# Sheet1.net
KiCad netlist of a schematic drawn in Altium Designer
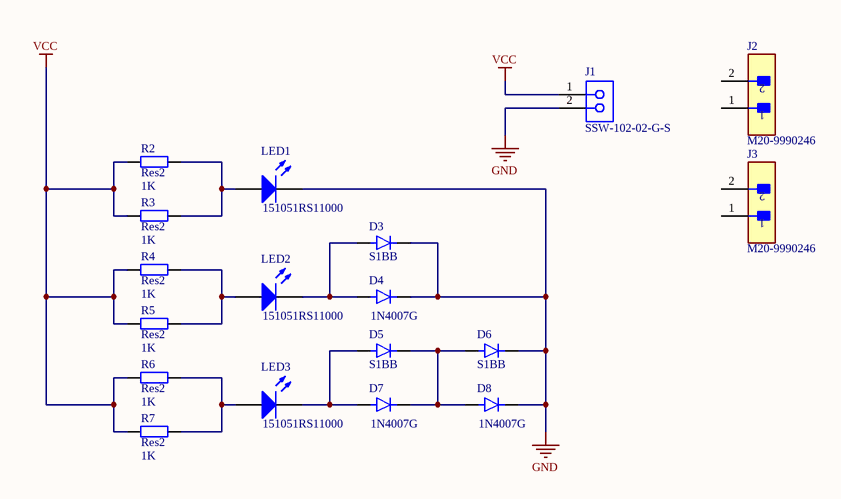
[diagram p0: Sheet1.SchDoc]

(export (version "E")
  (design (tool "Eeschema 10.0.6"))
  (components
    (comp (ref "D3")
      (value "S1BB")
      (footprint "S1BB:DIOM4336X265N")
      (fields (field (name "MF") "{'manufacturer': u'Taiwan Semiconductor'}"))
      (libsource (lib "*") (part "S1BB"))
    )
    (comp (ref "D4")
      (value "1N4007G")
      (footprint "1N4007G:DIOAD1036W78L470D235")
      (fields (field (name "MF") "{'manufacturer': u'ON Semiconductor'}"))
      (libsource (lib "*") (part "1N4007G"))
    )
    (comp (ref "D5")
      (value "S1BB")
      (footprint "S1BB:DIOM4336X265N")
      (fields (field (name "MF") "{'manufacturer': u'Taiwan Semiconductor'}"))
      (libsource (lib "*") (part "S1BB"))
    )
    (comp (ref "D6")
      (value "S1BB")
      (footprint "S1BB:DIOM4336X265N")
      (fields (field (name "MF") "{'manufacturer': u'Taiwan Semiconductor'}"))
      (libsource (lib "*") (part "S1BB"))
    )
    (comp (ref "D7")
      (value "1N4007G")
      (footprint "1N4007G:DIOAD1036W78L470D235")
      (fields (field (name "MF") "{'manufacturer': u'ON Semiconductor'}"))
      (libsource (lib "*") (part "1N4007G"))
    )
    (comp (ref "D8")
      (value "1N4007G")
      (footprint "1N4007G:DIOAD1036W78L470D235")
      (fields (field (name "MF") "{'manufacturer': u'ON Semiconductor'}"))
      (libsource (lib "*") (part "1N4007G"))
    )
    (comp (ref "J1")
      (value "SSW-102-02-G-S")
      (footprint "SMTC-SSW-102-02-X-S")
      (description "SQ Post Socket, Through-hole, Vertical, -55 to 125 degC, 2.54 mm Pitch, 2-Pin, Female, RoHS")
      (fields (field (name "MANUFACTURER") "Samtec"))
      (libsource (lib "Altium Content Vault") (part "SMTC-SSW-102-02-X-S-X"))
    )
    (comp (ref "J2")
      (value "M20-9990246")
      (footprint "FP-M20-9990246-MFG")
      (description "Connector Header Through Hole 2 position 0.100\" (2.54mm)")
      (fields (field (name "OCTOPART") "https://octopart.com/m20-9990246-harwin-2590635"))
      (libsource (lib "Altium Content Vault") (part "3bc925449376181038e59eaffc5286c"))
    )
    (comp (ref "J3")
      (value "M20-9990246")
      (footprint "FP-M20-9990246-MFG")
      (description "Connector Header Through Hole 2 position 0.100\" (2.54mm)")
      (fields (field (name "OCTOPART") "https://octopart.com/m20-9990246-harwin-2590635"))
      (libsource (lib "Altium Content Vault") (part "3bc925449376181038e59eaffc5286c"))
    )
    (comp (ref "LED1")
      (value "151051RS11000")
      (footprint "Type 5mm")
      (description "THT LED round mono-color color lens, WL-TMRW, Red")
      (fields (field (name "MANUFACTURER") "Wuerth Elektronik"))
      (libsource (lib "Altium Content Vault") (part "WE-LED_K1A2-2"))
    )
    (comp (ref "LED2")
      (value "151051RS11000")
      (footprint "Type 5mm")
      (description "THT LED round mono-color color lens, WL-TMRW, Red")
      (fields (field (name "MANUFACTURER") "Wuerth Elektronik"))
      (libsource (lib "Altium Content Vault") (part "WE-LED_K1A2-2"))
    )
    (comp (ref "LED3")
      (value "151051RS11000")
      (footprint "Type 5mm")
      (description "THT LED round mono-color color lens, WL-TMRW, Red")
      (fields (field (name "MANUFACTURER") "Wuerth Elektronik"))
      (libsource (lib "Altium Content Vault") (part "WE-LED_K1A2-2"))
    )
    (comp (ref "R2")
      (value "Res2")
      (footprint "AXIAL-0.5")
      (description "Resistor")
      (fields (field (name "ALTIUM_VALUE") "1K") (field (name "PUBLISHER") "Altium Limited"))
      (libsource (lib "Miscellaneous Devices") (part "Res2"))
    )
    (comp (ref "R3")
      (value "Res2")
      (footprint "C1206")
      (description "Resistor")
      (fields (field (name "ALTIUM_VALUE") "1K") (field (name "PUBLISHER") "Altium Limited"))
      (libsource (lib "Miscellaneous Devices") (part "Res2"))
    )
    (comp (ref "R4")
      (value "Res2")
      (footprint "AXIAL-0.5")
      (description "Resistor")
      (fields (field (name "ALTIUM_VALUE") "1K") (field (name "PUBLISHER") "Altium Limited"))
      (libsource (lib "Miscellaneous Devices") (part "Res2"))
    )
    (comp (ref "R5")
      (value "Res2")
      (footprint "C1206")
      (description "Resistor")
      (fields (field (name "ALTIUM_VALUE") "1K") (field (name "PUBLISHER") "Altium Limited"))
      (libsource (lib "Miscellaneous Devices") (part "Res2"))
    )
    (comp (ref "R6")
      (value "Res2")
      (footprint "AXIAL-0.5")
      (description "Resistor")
      (fields (field (name "ALTIUM_VALUE") "1K") (field (name "PUBLISHER") "Altium Limited"))
      (libsource (lib "Miscellaneous Devices") (part "Res2"))
    )
    (comp (ref "R7")
      (value "Res2")
      (footprint "C1206")
      (description "Resistor")
      (fields (field (name "ALTIUM_VALUE") "1K") (field (name "PUBLISHER") "Altium Limited"))
      (libsource (lib "Miscellaneous Devices") (part "Res2"))
    )
  )
  (nets
    (net (code "1") (name "GND") (class "Default")
      (node (ref "D3") (pin "C") (pinfunction "K_C") (pintype "passive"))
      (node (ref "D4") (pin "C") (pinfunction "K_C") (pintype "passive"))
      (node (ref "D6") (pin "C") (pinfunction "K_C") (pintype "passive"))
      (node (ref "D8") (pin "C") (pinfunction "K_C") (pintype "passive"))
      (node (ref "J1") (pin "2") (pinfunction "2_2") (pintype "passive"))
      (node (ref "LED1") (pin "1") (pinfunction "K_1") (pintype "passive"))
    )
    (net (code "2") (name "Net-(D5-K)") (class "Default")
      (node (ref "D5") (pin "C") (pinfunction "K_C") (pintype "passive"))
      (node (ref "D6") (pin "A") (pinfunction "A_A") (pintype "passive"))
      (node (ref "D7") (pin "C") (pinfunction "K_C") (pintype "passive"))
      (node (ref "D8") (pin "A") (pinfunction "A_A") (pintype "passive"))
    )
    (net (code "3") (name "Net-(LED1-A)") (class "Default")
      (node (ref "LED1") (pin "2") (pinfunction "A_2") (pintype "passive"))
      (node (ref "R2") (pin "2") (pinfunction "2_2") (pintype "passive"))
      (node (ref "R3") (pin "2") (pinfunction "2_2") (pintype "passive"))
    )
    (net (code "4") (name "Net-(LED2-A)") (class "Default")
      (node (ref "LED2") (pin "2") (pinfunction "A_2") (pintype "passive"))
      (node (ref "R4") (pin "2") (pinfunction "2_2") (pintype "passive"))
      (node (ref "R5") (pin "2") (pinfunction "2_2") (pintype "passive"))
    )
    (net (code "5") (name "Net-(LED2-K)") (class "Default")
      (node (ref "D3") (pin "A") (pinfunction "A_A") (pintype "passive"))
      (node (ref "D4") (pin "A") (pinfunction "A_A") (pintype "passive"))
      (node (ref "LED2") (pin "1") (pinfunction "K_1") (pintype "passive"))
    )
    (net (code "6") (name "Net-(LED3-A)") (class "Default")
      (node (ref "LED3") (pin "2") (pinfunction "A_2") (pintype "passive"))
      (node (ref "R6") (pin "2") (pinfunction "2_2") (pintype "passive"))
      (node (ref "R7") (pin "2") (pinfunction "2_2") (pintype "passive"))
    )
    (net (code "7") (name "Net-(LED3-K)") (class "Default")
      (node (ref "D5") (pin "A") (pinfunction "A_A") (pintype "passive"))
      (node (ref "D7") (pin "A") (pinfunction "A_A") (pintype "passive"))
      (node (ref "LED3") (pin "1") (pinfunction "K_1") (pintype "passive"))
    )
    (net (code "8") (name "VCC") (class "Default")
      (node (ref "J1") (pin "1") (pinfunction "1_1") (pintype "passive"))
      (node (ref "R2") (pin "1") (pinfunction "1_1") (pintype "passive"))
      (node (ref "R3") (pin "1") (pinfunction "1_1") (pintype "passive"))
      (node (ref "R4") (pin "1") (pinfunction "1_1") (pintype "passive"))
      (node (ref "R5") (pin "1") (pinfunction "1_1") (pintype "passive"))
      (node (ref "R6") (pin "1") (pinfunction "1_1") (pintype "passive"))
      (node (ref "R7") (pin "1") (pinfunction "1_1") (pintype "passive"))
    )
    (net (code "9") (name "unconnected-(J2-Pad1)") (class "Default")
      (node (ref "J2") (pin "1") (pinfunction "1_1") (pintype "passive"))
    )
    (net (code "10") (name "unconnected-(J2-Pad2)") (class "Default")
      (node (ref "J2") (pin "2") (pinfunction "2_2") (pintype "passive"))
    )
    (net (code "11") (name "unconnected-(J3-Pad1)") (class "Default")
      (node (ref "J3") (pin "1") (pinfunction "1_1") (pintype "passive"))
    )
    (net (code "12") (name "unconnected-(J3-Pad2)") (class "Default")
      (node (ref "J3") (pin "2") (pinfunction "2_2") (pintype "passive"))
    )
  )
)
